# ECG.net
KiCad netlist of a schematic drawn in EAGLE
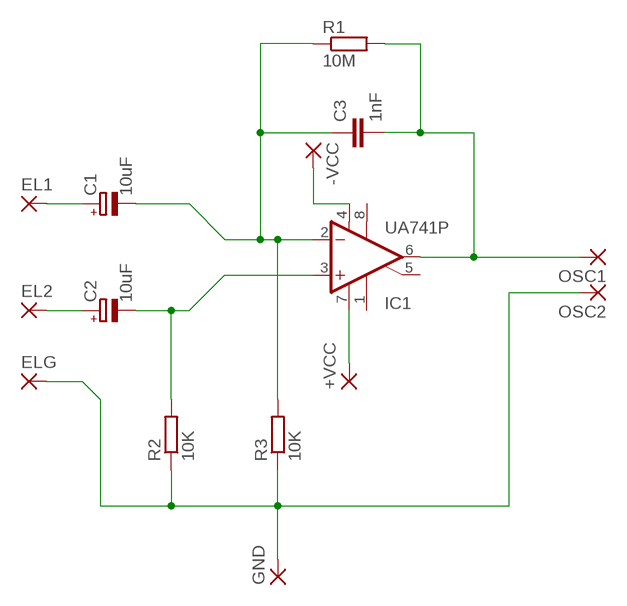
[diagram p0: schematic, sheet 1]

(export (version "E")
  (design (tool "Eeschema 10.0.6"))
  (components
    (comp (ref "+VCC")
      (value "1,6/0,8")
      (footprint "eagle-import:1,6_0,8")
      (libsource (lib "eagle-import") (part "1,6/0,8"))
    )
    (comp (ref "-VCC")
      (value "1,6/0,8")
      (footprint "eagle-import:1,6_0,8")
      (libsource (lib "eagle-import") (part "1,6/0,8"))
    )
    (comp (ref "C1")
      (value "10uF")
      (footprint "eagle-import:E1,8-4")
      (libsource (lib "eagle-import") (part "CPOL-EUE1.8-4"))
    )
    (comp (ref "C2")
      (value "10uF")
      (footprint "eagle-import:E1,8-4")
      (libsource (lib "eagle-import") (part "CPOL-EUE1.8-4"))
    )
    (comp (ref "C3")
      (value "1nF")
      (footprint "eagle-import:C025-024X044")
      (libsource (lib "eagle-import") (part "C-EU025-024X044"))
    )
    (comp (ref "EL1")
      (value "1,6/0,8")
      (footprint "eagle-import:1,6_0,8")
      (libsource (lib "eagle-import") (part "1,6/0,8"))
    )
    (comp (ref "EL2")
      (value "1,6/0,8")
      (footprint "eagle-import:1,6_0,8")
      (libsource (lib "eagle-import") (part "1,6/0,8"))
    )
    (comp (ref "ELG")
      (value "1,6/0,8")
      (footprint "eagle-import:1,6_0,8")
      (libsource (lib "eagle-import") (part "1,6/0,8"))
    )
    (comp (ref "GND")
      (value "1,6/0,8")
      (footprint "eagle-import:1,6_0,8")
      (libsource (lib "eagle-import") (part "1,6/0,8"))
    )
    (comp (ref "IC1")
      (value "UA741P")
      (footprint "eagle-import:DIL08")
      (libsource (lib "eagle-import") (part "741PUA"))
    )
    (comp (ref "OSC1")
      (value "1,6/0,8")
      (footprint "eagle-import:1,6_0,8")
      (libsource (lib "eagle-import") (part "1,6/0,8"))
    )
    (comp (ref "OSC2")
      (value "1,6/0,8")
      (footprint "eagle-import:1,6_0,8")
      (libsource (lib "eagle-import") (part "1,6/0,8"))
    )
    (comp (ref "R1")
      (value "10M")
      (footprint "eagle-import:0207_7")
      (libsource (lib "eagle-import") (part "R-EU_0207/7"))
    )
    (comp (ref "R2")
      (value "10K")
      (footprint "eagle-import:0207_7")
      (libsource (lib "eagle-import") (part "R-EU_0207/7"))
    )
    (comp (ref "R3")
      (value "10K")
      (footprint "eagle-import:0207_7")
      (libsource (lib "eagle-import") (part "R-EU_0207/7"))
    )
  )
  (nets
    (net (code "1") (name "Net-(+VCC-P)") (class "Default")
      (node (ref "+VCC") (pin "1") (pinfunction "P_1") (pintype "passive"))
      (node (ref "IC1") (pin "7") (pinfunction "V+_7") (pintype "power_in"))
    )
    (net (code "2") (name "Net-(-VCC-P)") (class "Default")
      (node (ref "-VCC") (pin "1") (pinfunction "P_1") (pintype "passive"))
      (node (ref "IC1") (pin "4") (pinfunction "V-_4") (pintype "power_in"))
    )
    (net (code "3") (name "Net-(EL1-P)") (class "Default")
      (node (ref "C1") (pin "+") (pinfunction "+_+") (pintype "passive"))
      (node (ref "EL1") (pin "1") (pinfunction "P_1") (pintype "passive"))
    )
    (net (code "4") (name "Net-(EL2-P)") (class "Default")
      (node (ref "C2") (pin "+") (pinfunction "+_+") (pintype "passive"))
      (node (ref "EL2") (pin "1") (pinfunction "P_1") (pintype "passive"))
    )
    (net (code "5") (name "Net-(ELG-P)") (class "Default")
      (node (ref "ELG") (pin "1") (pinfunction "P_1") (pintype "passive"))
      (node (ref "GND") (pin "1") (pinfunction "P_1") (pintype "passive"))
      (node (ref "OSC2") (pin "1") (pinfunction "P_1") (pintype "passive"))
      (node (ref "R2") (pin "1") (pinfunction "1_1") (pintype "passive"))
      (node (ref "R3") (pin "1") (pinfunction "1_1") (pintype "passive"))
    )
    (net (code "6") (name "Net-(IC1-+IN)") (class "Default")
      (node (ref "C2") (pin "-") (pinfunction "-_-") (pintype "passive"))
      (node (ref "IC1") (pin "3") (pinfunction "+IN_3") (pintype "input"))
      (node (ref "R2") (pin "2") (pinfunction "2_2") (pintype "passive"))
    )
    (net (code "7") (name "Net-(IC1--IN)") (class "Default")
      (node (ref "C1") (pin "-") (pinfunction "-_-") (pintype "passive"))
      (node (ref "C3") (pin "1") (pinfunction "1_1") (pintype "passive"))
      (node (ref "IC1") (pin "2") (pinfunction "-IN_2") (pintype "input"))
      (node (ref "R1") (pin "1") (pinfunction "1_1") (pintype "passive"))
      (node (ref "R3") (pin "2") (pinfunction "2_2") (pintype "passive"))
    )
    (net (code "8") (name "Net-(IC1-OUT)") (class "Default")
      (node (ref "C3") (pin "2") (pinfunction "2_2") (pintype "passive"))
      (node (ref "IC1") (pin "6") (pinfunction "OUT_6") (pintype "output"))
      (node (ref "OSC1") (pin "1") (pinfunction "P_1") (pintype "passive"))
      (node (ref "R1") (pin "2") (pinfunction "2_2") (pintype "passive"))
    )
    (net (code "9") (name "unconnected-(IC1-ON1-Pad1)") (class "Default")
      (node (ref "IC1") (pin "1") (pinfunction "ON1_1") (pintype "passive"))
    )
    (net (code "10") (name "unconnected-(IC1-ON2-Pad5)") (class "Default")
      (node (ref "IC1") (pin "5") (pinfunction "ON2_5") (pintype "passive"))
    )
    (net (code "11") (name "unconnected-(IC1-OPT-Pad8)") (class "Default")
      (node (ref "IC1") (pin "8") (pinfunction "OPT_8") (pintype "passive"))
    )
  )
)
